# wiring.net
KiCad netlist of a schematic drawn in EAGLE
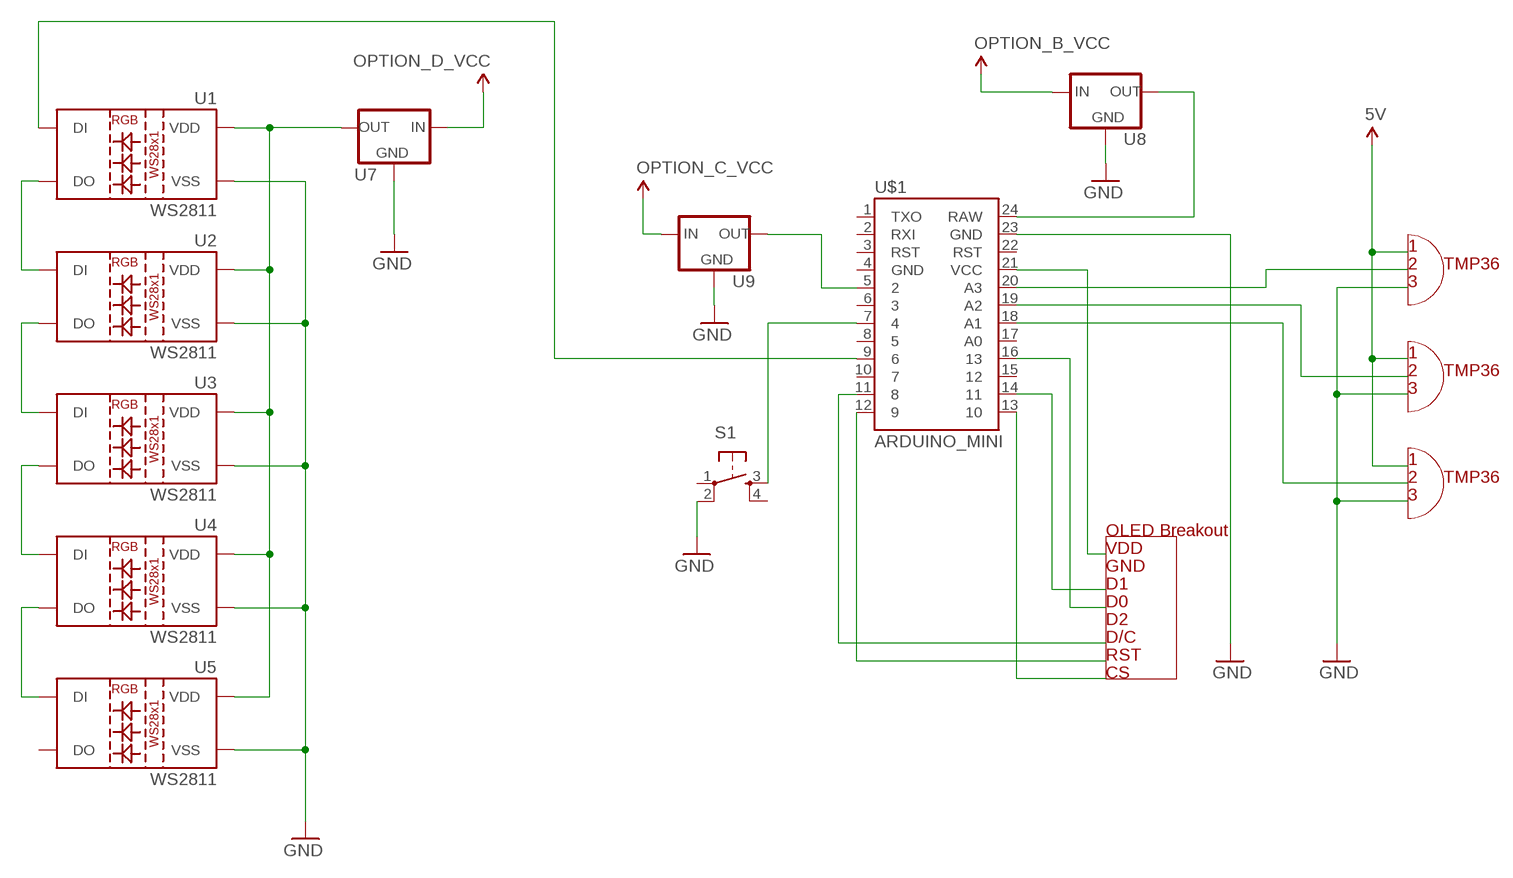
[diagram p0: schematic, sheet 1]

(export (version "E")
  (design (tool "Eeschema 10.0.6"))
  (components
    (comp (ref "S1")
      (value "TAC_SWITCHPTH")
      (footprint "eagle-import:TACTILE-PTH")
      (libsource (lib "eagle-import") (part "TAC_SWITCHPTH"))
    )
    (comp (ref "U$1")
      (value "ARDUINO_MINI")
      (footprint "eagle-import:ARDUINO_MINI")
      (libsource (lib "eagle-import") (part "ARDUINO_MINI"))
    )
    (comp (ref "U1")
      (value "WS2811")
      (footprint "eagle-import:LED-TRICOLOR-5050-IC")
      (libsource (lib "eagle-import") (part "LED-TRICOLOR-5050-ICWS2811"))
    )
    (comp (ref "U2")
      (value "WS2811")
      (footprint "eagle-import:LED-TRICOLOR-5050-IC")
      (libsource (lib "eagle-import") (part "LED-TRICOLOR-5050-ICWS2811"))
    )
    (comp (ref "U3")
      (value "WS2811")
      (footprint "eagle-import:LED-TRICOLOR-5050-IC")
      (libsource (lib "eagle-import") (part "LED-TRICOLOR-5050-ICWS2811"))
    )
    (comp (ref "U4")
      (value "WS2811")
      (footprint "eagle-import:LED-TRICOLOR-5050-IC")
      (libsource (lib "eagle-import") (part "LED-TRICOLOR-5050-ICWS2811"))
    )
    (comp (ref "U5")
      (value "WS2811")
      (footprint "eagle-import:LED-TRICOLOR-5050-IC")
      (libsource (lib "eagle-import") (part "LED-TRICOLOR-5050-ICWS2811"))
    )
    (comp (ref "U7")
      (value "V_REG_78XXSIDE")
      (footprint "eagle-import:78XXL")
      (libsource (lib "eagle-import") (part "V_REG_78XXSIDE"))
    )
    (comp (ref "U8")
      (value "V_REG_78XXSIDE")
      (footprint "eagle-import:78XXL")
      (libsource (lib "eagle-import") (part "V_REG_78XXSIDE"))
    )
    (comp (ref "U9")
      (value "V_REG_78XXSIDE")
      (footprint "eagle-import:78XXL")
      (libsource (lib "eagle-import") (part "V_REG_78XXSIDE"))
    )
  )
  (nets
    (net (code "1") (name "5V") (class "Default")
      (node (ref "U7") (pin "IN") (pinfunction "IN_IN") (pintype "input"))
      (node (ref "U8") (pin "IN") (pinfunction "IN_IN") (pintype "input"))
      (node (ref "U9") (pin "IN") (pinfunction "IN_IN") (pintype "input"))
    )
    (net (code "2") (name "GND") (class "Default")
      (node (ref "S1") (pin "2") (pinfunction "2_2") (pintype "passive"))
      (node (ref "U$1") (pin "23") (pinfunction "GND_23") (pintype "bidirectional"))
      (node (ref "U1") (pin "6") (pinfunction "VSS_6") (pintype "bidirectional"))
      (node (ref "U2") (pin "6") (pinfunction "VSS_6") (pintype "bidirectional"))
      (node (ref "U3") (pin "6") (pinfunction "VSS_6") (pintype "bidirectional"))
      (node (ref "U4") (pin "6") (pinfunction "VSS_6") (pintype "bidirectional"))
      (node (ref "U5") (pin "6") (pinfunction "VSS_6") (pintype "bidirectional"))
      (node (ref "U7") (pin "GND") (pinfunction "GND_GND") (pintype "input"))
      (node (ref "U8") (pin "GND") (pinfunction "GND_GND") (pintype "input"))
      (node (ref "U9") (pin "GND") (pinfunction "GND_GND") (pintype "input"))
    )
    (net (code "3") (name "Net-(U$1-2)") (class "Default")
      (node (ref "U$1") (pin "5") (pinfunction "2_5") (pintype "bidirectional"))
      (node (ref "U9") (pin "OUT") (pinfunction "OUT_OUT") (pintype "passive"))
    )
    (net (code "4") (name "Net-(U$1-4)") (class "Default")
      (node (ref "S1") (pin "3") (pinfunction "3_3") (pintype "passive"))
      (node (ref "U$1") (pin "7") (pinfunction "4_7") (pintype "bidirectional"))
    )
    (net (code "5") (name "Net-(U$1-6)") (class "Default")
      (node (ref "U$1") (pin "9") (pinfunction "6_9") (pintype "bidirectional"))
      (node (ref "U1") (pin "2") (pinfunction "DI_2") (pintype "bidirectional"))
    )
    (net (code "6") (name "Net-(U$1-RAW)") (class "Default")
      (node (ref "U$1") (pin "24") (pinfunction "RAW_24") (pintype "bidirectional"))
      (node (ref "U8") (pin "OUT") (pinfunction "OUT_OUT") (pintype "passive"))
    )
    (net (code "7") (name "Net-(U1-DO)") (class "Default")
      (node (ref "U1") (pin "1") (pinfunction "DO_1") (pintype "bidirectional"))
      (node (ref "U2") (pin "2") (pinfunction "DI_2") (pintype "bidirectional"))
    )
    (net (code "8") (name "Net-(U1-VDD-Pad3)") (class "Default")
      (node (ref "U1") (pin "3") (pinfunction "VDD_3") (pintype "bidirectional"))
      (node (ref "U1") (pin "5") (pinfunction "VDD_5") (pintype "bidirectional"))
      (node (ref "U2") (pin "3") (pinfunction "VDD_3") (pintype "bidirectional"))
      (node (ref "U2") (pin "5") (pinfunction "VDD_5") (pintype "bidirectional"))
      (node (ref "U3") (pin "3") (pinfunction "VDD_3") (pintype "bidirectional"))
      (node (ref "U3") (pin "5") (pinfunction "VDD_5") (pintype "bidirectional"))
      (node (ref "U4") (pin "3") (pinfunction "VDD_3") (pintype "bidirectional"))
      (node (ref "U4") (pin "5") (pinfunction "VDD_5") (pintype "bidirectional"))
      (node (ref "U5") (pin "3") (pinfunction "VDD_3") (pintype "bidirectional"))
      (node (ref "U5") (pin "5") (pinfunction "VDD_5") (pintype "bidirectional"))
      (node (ref "U7") (pin "OUT") (pinfunction "OUT_OUT") (pintype "passive"))
    )
    (net (code "9") (name "Net-(U2-DO)") (class "Default")
      (node (ref "U2") (pin "1") (pinfunction "DO_1") (pintype "bidirectional"))
      (node (ref "U3") (pin "2") (pinfunction "DI_2") (pintype "bidirectional"))
    )
    (net (code "10") (name "Net-(U3-DO)") (class "Default")
      (node (ref "U3") (pin "1") (pinfunction "DO_1") (pintype "bidirectional"))
      (node (ref "U4") (pin "2") (pinfunction "DI_2") (pintype "bidirectional"))
    )
    (net (code "11") (name "Net-(U4-DO)") (class "Default")
      (node (ref "U4") (pin "1") (pinfunction "DO_1") (pintype "bidirectional"))
      (node (ref "U5") (pin "2") (pinfunction "DI_2") (pintype "bidirectional"))
    )
    (net (code "12") (name "unconnected-(S1-Pad1)") (class "Default")
      (node (ref "S1") (pin "1") (pinfunction "1_1") (pintype "passive"))
    )
    (net (code "13") (name "unconnected-(S1-Pad4)") (class "Default")
      (node (ref "S1") (pin "4") (pinfunction "4_4") (pintype "passive"))
    )
    (net (code "14") (name "unconnected-(U$1-3-Pad6)") (class "Default")
      (node (ref "U$1") (pin "6") (pinfunction "3_6") (pintype "bidirectional"))
    )
    (net (code "15") (name "unconnected-(U$1-5-Pad8)") (class "Default")
      (node (ref "U$1") (pin "8") (pinfunction "5_8") (pintype "bidirectional"))
    )
    (net (code "16") (name "unconnected-(U$1-7-Pad10)") (class "Default")
      (node (ref "U$1") (pin "10") (pinfunction "7_10") (pintype "bidirectional"))
    )
    (net (code "17") (name "unconnected-(U$1-8-Pad11)") (class "Default")
      (node (ref "U$1") (pin "11") (pinfunction "8_11") (pintype "bidirectional"))
    )
    (net (code "18") (name "unconnected-(U$1-9-Pad12)") (class "Default")
      (node (ref "U$1") (pin "12") (pinfunction "9_12") (pintype "bidirectional"))
    )
    (net (code "19") (name "unconnected-(U$1-10-Pad13)") (class "Default")
      (node (ref "U$1") (pin "13") (pinfunction "10_13") (pintype "bidirectional"))
    )
    (net (code "20") (name "unconnected-(U$1-11-Pad14)") (class "Default")
      (node (ref "U$1") (pin "14") (pinfunction "11_14") (pintype "bidirectional"))
    )
    (net (code "21") (name "unconnected-(U$1-12-Pad15)") (class "Default")
      (node (ref "U$1") (pin "15") (pinfunction "12_15") (pintype "bidirectional"))
    )
    (net (code "22") (name "unconnected-(U$1-13-Pad16)") (class "Default")
      (node (ref "U$1") (pin "16") (pinfunction "13_16") (pintype "bidirectional"))
    )
    (net (code "23") (name "unconnected-(U$1-A0-Pad17)") (class "Default")
      (node (ref "U$1") (pin "17") (pinfunction "A0_17") (pintype "bidirectional"))
    )
    (net (code "24") (name "unconnected-(U$1-A1-Pad18)") (class "Default")
      (node (ref "U$1") (pin "18") (pinfunction "A1_18") (pintype "bidirectional"))
    )
    (net (code "25") (name "unconnected-(U$1-A2-Pad19)") (class "Default")
      (node (ref "U$1") (pin "19") (pinfunction "A2_19") (pintype "bidirectional"))
    )
    (net (code "26") (name "unconnected-(U$1-A3-Pad20)") (class "Default")
      (node (ref "U$1") (pin "20") (pinfunction "A3_20") (pintype "bidirectional"))
    )
    (net (code "27") (name "unconnected-(U$1-GND-Pad4)") (class "Default")
      (node (ref "U$1") (pin "4") (pinfunction "GND_4") (pintype "bidirectional"))
    )
    (net (code "28") (name "unconnected-(U$1-RST-Pad3)") (class "Default")
      (node (ref "U$1") (pin "3") (pinfunction "RST_3") (pintype "bidirectional"))
    )
    (net (code "29") (name "unconnected-(U$1-RST-Pad22)") (class "Default")
      (node (ref "U$1") (pin "22") (pinfunction "RST_22") (pintype "bidirectional"))
    )
    (net (code "30") (name "unconnected-(U$1-RXI-Pad2)") (class "Default")
      (node (ref "U$1") (pin "2") (pinfunction "RXI_2") (pintype "bidirectional"))
    )
    (net (code "31") (name "unconnected-(U$1-TXO-Pad1)") (class "Default")
      (node (ref "U$1") (pin "1") (pinfunction "TXO_1") (pintype "bidirectional"))
    )
    (net (code "32") (name "unconnected-(U$1-VCC-Pad21)") (class "Default")
      (node (ref "U$1") (pin "21") (pinfunction "VCC_21") (pintype "bidirectional"))
    )
    (net (code "33") (name "unconnected-(U5-DO-Pad1)") (class "Default")
      (node (ref "U5") (pin "1") (pinfunction "DO_1") (pintype "bidirectional"))
    )
  )
)
